# Mixer_coupler.net
KiCad netlist of a schematic drawn in Altium Designer
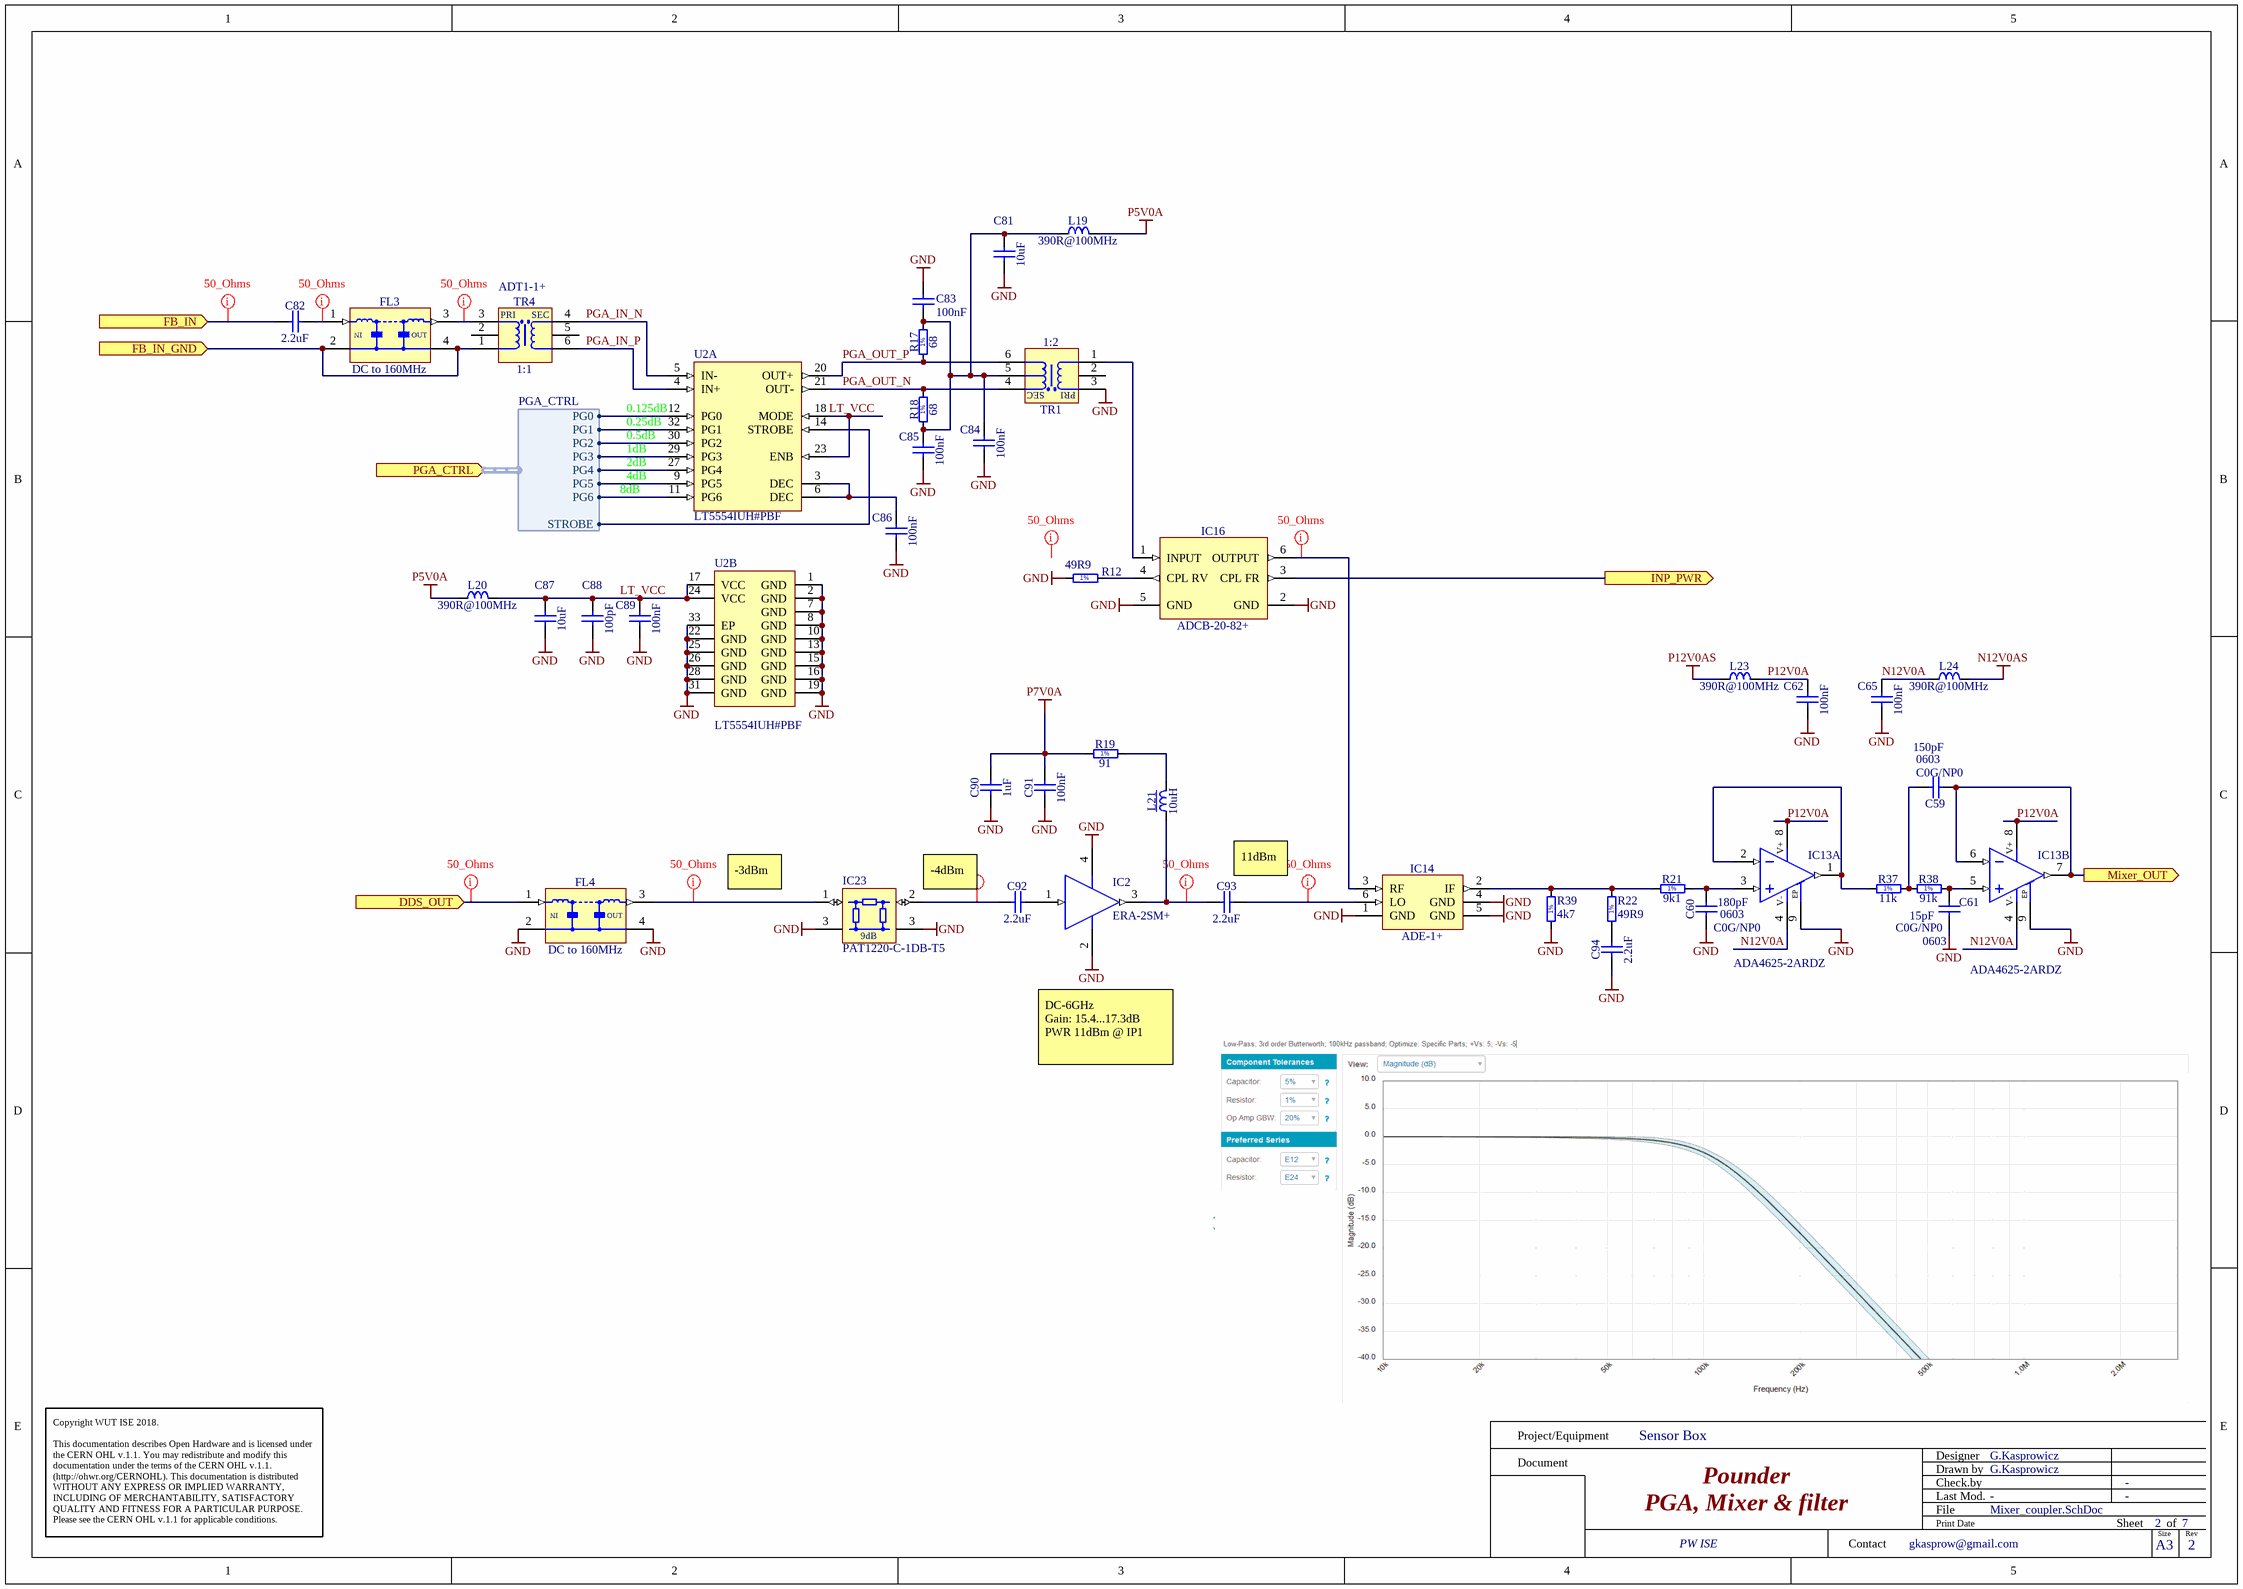
[diagram p0: Mixer_coupler.SchDoc]

(export (version "E")
  (design (tool "Eeschema 10.0.6"))
  (components
    (comp (ref "C59")
      (value "150pF")
      (footprint "CAPC1608X87N")
      (description "Non-polarised capacitor")
      (fields
        (field (name "PART NUMBER") "CC0603_150PF_50V_1%_NP0")
        (field (name "VOLTAGE") "50V")
        (field (name "TC") "C0G/NP0")
        (field (name "CASE") "0603")
        (field (name "AUTHOR") "CERN DEM MR")
      )
      (libsource (lib "Capacitors") (part "Capacitor - non polarized"))
    )
    (comp (ref "C60")
      (value "180pF")
      (footprint "CAPC1608X87N")
      (description "Non-polarised capacitor")
      (fields
        (field (name "PART NUMBER") "CC0603_180PF_50V_5%_NP0")
        (field (name "VOLTAGE") "50V")
        (field (name "TC") "C0G/NP0")
        (field (name "CASE") "0603")
        (field (name "AUTHOR") "CERN DEM JLC")
      )
      (libsource (lib "Capacitors") (part "Capacitor - non polarized"))
    )
    (comp (ref "C61")
      (value "15pF")
      (footprint "CAPC1608X87N")
      (description "Non-polarised capacitor")
      (fields
        (field (name "PART NUMBER") "CC0603_15PF_50V_5%_NP0")
        (field (name "VOLTAGE") "50V")
        (field (name "TC") "C0G/NP0")
        (field (name "CASE") "0603")
        (field (name "AUTHOR") "CERN DEM JLC")
      )
      (libsource (lib "Capacitors") (part "Capacitor - non polarized"))
    )
    (comp (ref "C62")
      (value "100nF")
      (footprint "CAPC1005X55N")
      (description "Non-polarised capacitor")
      (fields
        (field (name "PART NUMBER") "CC0402_100NF_16V_10%_X7R")
        (field (name "VOLTAGE") "16V")
        (field (name "AUTHOR") "CERN DEM JLC")
      )
      (libsource (lib "Capacitors") (part "Capacitor - non polarized"))
    )
    (comp (ref "C65")
      (value "100nF")
      (footprint "CAPC1005X55N")
      (description "Non-polarised capacitor")
      (fields
        (field (name "PART NUMBER") "CC0402_100NF_16V_10%_X7R")
        (field (name "VOLTAGE") "16V")
        (field (name "AUTHOR") "CERN DEM JLC")
      )
      (libsource (lib "Capacitors") (part "Capacitor - non polarized"))
    )
    (comp (ref "C81")
      (value "10uF")
      (footprint "CAPC1608X80N")
      (description "Non-polarised capacitor")
      (fields
        (field (name "PART NUMBER") "CC0603_10UF_16V_20%_X5R")
        (field (name "VOLTAGE") "16V")
        (field (name "AUTHOR") "CERN DEM MR")
      )
      (libsource (lib "Capacitors") (part "Capacitor - non polarized"))
    )
    (comp (ref "C82")
      (value "2.2uF")
      (footprint "CAPC1005X55N")
      (description "Non-polarised capacitor")
      (fields
        (field (name "PART NUMBER") "CC0402_2.2UF_6.3V_10%_X5R")
        (field (name "VOLTAGE") "6.3V")
        (field (name "AUTHOR") "CERN DEM JMW")
      )
      (libsource (lib "Capacitors") (part "Capacitor - non polarized"))
    )
    (comp (ref "C83")
      (value "100nF")
      (footprint "CAPC1005X55N")
      (description "Non-polarised capacitor")
      (fields
        (field (name "PART NUMBER") "CC0402_100NF_16V_10%_X7R")
        (field (name "VOLTAGE") "16V")
        (field (name "AUTHOR") "CERN DEM JLC")
      )
      (libsource (lib "Capacitors") (part "Capacitor - non polarized"))
    )
    (comp (ref "C84")
      (value "100nF")
      (footprint "CAPC1005X55N")
      (description "Non-polarised capacitor")
      (fields
        (field (name "PART NUMBER") "CC0402_100NF_16V_10%_X7R")
        (field (name "VOLTAGE") "16V")
        (field (name "AUTHOR") "CERN DEM JLC")
      )
      (libsource (lib "Capacitors") (part "Capacitor - non polarized"))
    )
    (comp (ref "C85")
      (value "100nF")
      (footprint "CAPC1005X55N")
      (description "Non-polarised capacitor")
      (fields
        (field (name "PART NUMBER") "CC0402_100NF_16V_10%_X7R")
        (field (name "VOLTAGE") "16V")
        (field (name "AUTHOR") "CERN DEM JLC")
      )
      (libsource (lib "Capacitors") (part "Capacitor - non polarized"))
    )
    (comp (ref "C86")
      (value "100nF")
      (footprint "CAPC1005X55N")
      (description "Non-polarised capacitor")
      (fields
        (field (name "PART NUMBER") "CC0402_100NF_16V_10%_X7R")
        (field (name "VOLTAGE") "16V")
        (field (name "AUTHOR") "CERN DEM JLC")
      )
      (libsource (lib "Capacitors") (part "Capacitor - non polarized"))
    )
    (comp (ref "C87")
      (value "10uF")
      (footprint "CAPC1608X80N")
      (description "Non-polarised capacitor")
      (fields
        (field (name "PART NUMBER") "CC0603_10UF_16V_20%_X5R")
        (field (name "VOLTAGE") "16V")
        (field (name "AUTHOR") "CERN DEM MR")
      )
      (libsource (lib "Capacitors") (part "Capacitor - non polarized"))
    )
    (comp (ref "C88")
      (value "100pF")
      (footprint "CAPC1005X55N")
      (description "Non-polarised capacitor")
      (fields
        (field (name "PART NUMBER") "CC0402_100PF_50V_5%_C0G")
        (field (name "VOLTAGE") "50V")
        (field (name "AUTHOR") "CERN DEM JLC")
      )
      (libsource (lib "Capacitors") (part "Capacitor - non polarized"))
    )
    (comp (ref "C89")
      (value "100nF")
      (footprint "CAPC1005X55N")
      (description "Non-polarised capacitor")
      (fields
        (field (name "PART NUMBER") "CC0402_100NF_16V_10%_X7R")
        (field (name "VOLTAGE") "16V")
        (field (name "AUTHOR") "CERN DEM JLC")
      )
      (libsource (lib "Capacitors") (part "Capacitor - non polarized"))
    )
    (comp (ref "C90")
      (value "1uF")
      (footprint "CAPC2012X140N")
      (description "Non-polarised capacitor")
      (fields
        (field (name "PART NUMBER") "CC0805_1UF_35V_20%_X7R")
        (field (name "VOLTAGE") "35V")
        (field (name "AUTHOR") "CERN DEM JLC")
      )
      (libsource (lib "Capacitors") (part "Capacitor - non polarized"))
    )
    (comp (ref "C91")
      (value "100nF")
      (footprint "CAPC1005X55N")
      (description "Non-polarised capacitor")
      (fields
        (field (name "PART NUMBER") "CC0402_100NF_16V_10%_X5R")
        (field (name "VOLTAGE") "16V")
        (field (name "AUTHOR") "CERN DEM JLC")
      )
      (libsource (lib "Capacitors") (part "Capacitor - non polarized"))
    )
    (comp (ref "C92")
      (value "2.2uF")
      (footprint "CAPC1005X55N")
      (description "Non-polarised capacitor")
      (fields
        (field (name "PART NUMBER") "CC0402_2.2UF_6.3V_10%_X5R")
        (field (name "VOLTAGE") "6.3V")
        (field (name "AUTHOR") "CERN DEM JMW")
      )
      (libsource (lib "Capacitors") (part "Capacitor - non polarized"))
    )
    (comp (ref "C93")
      (value "2.2uF")
      (footprint "CAPC1005X55N")
      (description "Non-polarised capacitor")
      (fields
        (field (name "PART NUMBER") "CC0402_2.2UF_6.3V_10%_X5R")
        (field (name "VOLTAGE") "6.3V")
        (field (name "AUTHOR") "CERN DEM JMW")
      )
      (libsource (lib "Capacitors") (part "Capacitor - non polarized"))
    )
    (comp (ref "C94")
      (value "2.2uF")
      (footprint "CAPC1005X55N")
      (description "Non-polarised capacitor")
      (fields
        (field (name "PART NUMBER") "CC0402_2.2UF_6.3V_10%_X5R")
        (field (name "VOLTAGE") "6.3V")
        (field (name "AUTHOR") "CERN DEM JMW")
      )
      (libsource (lib "Capacitors") (part "Capacitor - non polarized"))
    )
    (comp (ref "FL3")
      (value "DC to 160MHz")
      (footprint "FIL_MINI-CIRCUITS_FV1206")
      (description "50 Ohm DC to 320MHz Low Pass Filter")
      (fields
        (field (name "PART NUMBER") "FIL_MINI-CIRCUITS_LFCN-160")
        (field (name "MANUFACTURER") "MINI-CIRCUITS")
        (field (name "AUTHOR") "CERN DEM JLC")
      )
      (libsource (lib "LIBRARY_SCH") (part "FIL_MINI-CIRCUITS_LFCN-320"))
    )
    (comp (ref "FL4")
      (value "DC to 160MHz")
      (footprint "FIL_MINI-CIRCUITS_FV1206")
      (description "50 Ohm DC to 320MHz Low Pass Filter")
      (fields
        (field (name "PART NUMBER") "FIL_MINI-CIRCUITS_LFCN-160")
        (field (name "MANUFACTURER") "MINI-CIRCUITS")
        (field (name "AUTHOR") "CERN DEM JLC")
      )
      (libsource (lib "LIBRARY_SCH") (part "FIL_MINI-CIRCUITS_LFCN-320"))
    )
    (comp (ref "IC2")
      (value "ERA-2SM+")
      (footprint "MINI-CIRCUITS_WW107")
      (description "Monolithic Amplifier")
      (fields (field (name "MANUFACTURER") "MINI-CIRCUITS") (field (name "AUTHOR") "CERN DEM JLC"))
      (libsource (lib "ICs And Semiconductors") (part "Monolithic Amplifier Type 1"))
    )
    (comp (ref "IC13")
      (value "ADA4625-2ARDZ")
      (footprint "SOIC127P600X175-9N-S229")
      (description "Dual Operational Amplifier With Exposed Pad")
      (fields (field (name "MANUFACTURER") "ANALOG DEVICES") (field (name "AUTHOR") "CERN DEM MR"))
      (libsource (lib "ICs And Semiconductors") (part "Operational Amplifier x2 Type1 EP"))
    )
    (comp (ref "IC14")
      (value "ADE-1+")
      (footprint "MACOM_SM-87")
      (description "5 to 2500 MHz E-Series Surface Mount Mixer")
      (fields (field (name "MANUFACTURER") "MACOM") (field (name "AUTHOR") "CERN DEM JLC"))
      (libsource (lib "ICs And Semiconductors") (part "MAMX-007238-CM25MH"))
    )
    (comp (ref "IC16")
      (value "ADCB-20-82+")
      (footprint "MINI-CIRCUITS_CD637")
      (description "50Ω,   20dB Coupling,    1 to 800 MHz")
      (fields (field (name "MANUFACTURER") "MINI-CIRCUITS") (field (name "AUTHOR") "CERN DEM MR"))
      (libsource (lib "ICs And Semiconductors") (part "ADPQ-2-250"))
    )
    (comp (ref "IC23")
      (value "PAT1220-C-1DB-T5")
      (footprint "SUSUMU_PAT1220")
      (description "DC to 10GHz, 100mw, 50 Ohm, 9dB, Precision chip attenuator")
      (fields (field (name "MANUFACTURER") "SUSUMU") (field (name "AUTHOR") "GK"))
      (libsource (lib "LIBRARY_SCH") (part "RF_PAT1220-C-9DB-T5"))
    )
    (comp (ref "L19")
      (value "390R@100MHz")
      (footprint "INDC1608X95N")
      (description "Inductor")
      (fields
        (field (name "PART NUMBER") "IND0603_TDK_MPZ1608R391A")
        (field (name "POWER") "1.2A")
        (field (name "AUTHOR") "CERN DEM JLC")
      )
      (libsource (lib "Inductors & Transformers") (part "Inductor"))
    )
    (comp (ref "L20")
      (value "390R@100MHz")
      (footprint "INDC1608X95N")
      (description "Inductor")
      (fields
        (field (name "PART NUMBER") "IND0603_TDK_MPZ1608R391A")
        (field (name "POWER") "1.2A")
        (field (name "AUTHOR") "CERN DEM JLC")
      )
      (libsource (lib "Inductors & Transformers") (part "Inductor"))
    )
    (comp (ref "L21")
      (value "10uH")
      (footprint "IND_MURATA_LQH32C")
      (description "Inductor With Core")
      (fields
        (field (name "PART NUMBER") "IND_10UH_10%_MURATA_LQH32CN100K33L")
        (field (name "POWER") "450mA")
        (field (name "AUTHOR") "CERN DEM JLC")
      )
      (libsource (lib "Inductors & Transformers") (part "Inductor With Magnetic core"))
    )
    (comp (ref "L23")
      (value "390R@100MHz")
      (footprint "INDC1608X95N")
      (description "Inductor")
      (fields
        (field (name "PART NUMBER") "IND0603_TDK_MPZ1608R391A")
        (field (name "POWER") "1.2A")
        (field (name "AUTHOR") "CERN DEM JLC")
      )
      (libsource (lib "Inductors & Transformers") (part "Inductor"))
    )
    (comp (ref "L24")
      (value "390R@100MHz")
      (footprint "INDC1608X95N")
      (description "Inductor")
      (fields
        (field (name "PART NUMBER") "IND0603_TDK_MPZ1608R391A")
        (field (name "POWER") "1.2A")
        (field (name "AUTHOR") "CERN DEM JLC")
      )
      (libsource (lib "Inductors & Transformers") (part "Inductor"))
    )
    (comp (ref "R12")
      (value "49R9")
      (footprint "RESC1005X40N")
      (description "Resistor - 1%")
      (fields
        (field (name "PART NUMBER") "R0402_49R9_1%_0.0625W_100PPM")
        (field (name "POWER") "0.0625W")
        (field (name "AUTHOR") "CERN DEM JLC")
      )
      (libsource (lib "Resistors") (part "Resistor - 1%"))
    )
    (comp (ref "R17")
      (value "68")
      (footprint "RESC1608X55N")
      (description "Resistor - 1%")
      (fields
        (field (name "PART NUMBER") "R0603_68R_1%_0.1W_100PPM")
        (field (name "POWER") "0.1W")
        (field (name "AUTHOR") "CERN DEM JLC")
      )
      (libsource (lib "Resistors") (part "Resistor - 1%"))
    )
    (comp (ref "R18")
      (value "68")
      (footprint "RESC1608X55N")
      (description "Resistor - 1%")
      (fields
        (field (name "PART NUMBER") "R0603_68R_1%_0.1W_100PPM")
        (field (name "POWER") "0.1W")
        (field (name "AUTHOR") "CERN DEM JLC")
      )
      (libsource (lib "Resistors") (part "Resistor - 1%"))
    )
    (comp (ref "R19")
      (value "91")
      (footprint "RESC3216X65N")
      (description "Resistor - 1%")
      (fields
        (field (name "PART NUMBER") "R1206_91R_1%_0.25W_100PPM")
        (field (name "POWER") "0.25W")
        (field (name "AUTHOR") "CERN DEM JLC")
      )
      (libsource (lib "Resistors") (part "Resistor - 1%"))
    )
    (comp (ref "R21")
      (value "9k1")
      (footprint "RESC1005X40N")
      (description "Resistor - 1%")
      (fields
        (field (name "PART NUMBER") "R0402_9K1_1%_0.0625W_100PPM")
        (field (name "POWER") "0.0625W")
        (field (name "AUTHOR") "CERN DEM JLC")
      )
      (libsource (lib "Resistors") (part "Resistor - 1%"))
    )
    (comp (ref "R22")
      (value "49R9")
      (footprint "RESC1005X40N")
      (description "Resistor - 1%")
      (fields
        (field (name "PART NUMBER") "R0402_49R9_1%_0.0625W_100PPM")
        (field (name "POWER") "0.0625W")
        (field (name "AUTHOR") "CERN DEM JLC")
      )
      (libsource (lib "Resistors") (part "Resistor - 1%"))
    )
    (comp (ref "R37")
      (value "11k")
      (footprint "RESC1608X55N")
      (description "Resistor - 1%")
      (fields
        (field (name "PART NUMBER") "R0603_11K_1%_0.1W_100PPM")
        (field (name "POWER") "0.1W")
        (field (name "AUTHOR") "CERN DEM JLC")
      )
      (libsource (lib "Resistors") (part "Resistor - 1%"))
    )
    (comp (ref "R38")
      (value "91k")
      (footprint "RESC1608X55N")
      (description "Resistor - 1%")
      (fields
        (field (name "PART NUMBER") "R0603_91K_1%_0.1W_100PPM")
        (field (name "POWER") "0.1W")
        (field (name "AUTHOR") "CERN DEM JLC")
      )
      (libsource (lib "Resistors") (part "Resistor - 1%"))
    )
    (comp (ref "R39")
      (value "4k7")
      (footprint "RESC1005X40N")
      (description "Resistor - 1%")
      (fields
        (field (name "PART NUMBER") "R0402_4K7_1%_0.0625W_100PPM")
        (field (name "POWER") "0.0625W")
        (field (name "AUTHOR") "CERN DEM JLC")
      )
      (libsource (lib "Resistors") (part "Resistor - 1%"))
    )
    (comp (ref "TR1")
      (value "1:2")
      (footprint "XFMR_MINI-CIRCUITS_CD542")
      (description "50 Ohms 0.4 To 450MHz RF Transformer")
      (fields
        (field (name "PART NUMBER") "XFMR_MINI-CIRCUITS_ADT2-1T+")
        (field (name "MANUFACTURER") "MINI-CIRCUITS")
        (field (name "AUTHOR") "CERN DEM MR")
      )
      (libsource (lib "Inductors & Transformers") (part "XFMR_MINI-CIRCUITS_ADT2-1T-1P+"))
    )
    (comp (ref "TR4")
      (value "1:1")
      (footprint "XFMR_MINI-CIRCUITS_CD542")
      (description "50 Ohm 0.15 To 400MHz RF Transformers")
      (fields
        (field (name "PART NUMBER") "XFMR_MINI-CIRCUITS_ADT1-1+")
        (field (name "MANUFACTURER") "MINI-CIRCUITS")
        (field (name "MANUFACTURER PART NUMBER") "ADT1-1+")
        (field (name "AUTHOR") "CERN DEM JLC")
      )
      (libsource (lib "Inductors & Transformers") (part "XFMR_MINI-CIRCUITS_ADT1-1+"))
    )
    (comp (ref "U2")
      (value "LT5554IUH#PBF")
      (footprint "LT-UH-32_N")
      (fields
        (field (name "LINEAR TECHNOLOGY PART NUMBER") "LT5554")
        (field (name "MANUFACTURER") "Linear Technology")
      )
      (libsource (lib "Altium Content Vault") (part "LT-LT5554-UH-32"))
    )
  )
  (nets
    (net (code "2") (name "/DDS_OUT") (class "Default")
      (node (ref "FL4") (pin "1") (pinfunction "RFIN_1") (pintype "input"))
    )
    (net (code "3") (name "/FB_IN") (class "Default")
      (node (ref "C82") (pin "1") (pinfunction "1_1") (pintype "passive"))
    )
    (net (code "4") (name "/FB_IN_GND") (class "Default")
      (node (ref "FL3") (pin "2") (pinfunction "GND_2") (pintype "power_in"))
      (node (ref "FL3") (pin "4") (pinfunction "GND_4") (pintype "power_in"))
      (node (ref "TR4") (pin "1") (pinfunction "P_1") (pintype "passive"))
    )
    (net (code "5") (name "/INP_PWR") (class "Default")
      (node (ref "IC16") (pin "3") (pinfunction "CPL_FR_3") (pintype "output"))
    )
    (net (code "6") (name "/LT_VCC") (class "Default")
      (node (ref "C87") (pin "2") (pinfunction "2_2") (pintype "passive"))
      (node (ref "C88") (pin "2") (pinfunction "2_2") (pintype "passive"))
      (node (ref "C89") (pin "2") (pinfunction "2_2") (pintype "passive"))
      (node (ref "L20") (pin "2") (pinfunction "2_2") (pintype "passive"))
      (node (ref "U2") (pin "17") (pinfunction "VCC_17") (pintype "power_in"))
      (node (ref "U2") (pin "18") (pinfunction "MODE_18") (pintype "input"))
      (node (ref "U2") (pin "23") (pinfunction "ENB_23") (pintype "input"))
      (node (ref "U2") (pin "24") (pinfunction "VCC_24") (pintype "power_in"))
    )
    (net (code "7") (name "/Mixer_OUT") (class "Default")
      (node (ref "C59") (pin "1") (pinfunction "1_1") (pintype "passive"))
      (node (ref "IC13") (pin "6") (pinfunction "IN-_6") (pintype "input"))
      (node (ref "IC13") (pin "7") (pinfunction "OUT_7") (pintype "output"))
    )
    (net (code "8") (name "/N12V0A") (class "Default")
      (node (ref "C65") (pin "2") (pinfunction "2_2") (pintype "passive"))
      (node (ref "IC13") (pin "4") (pinfunction "V-_4") (pintype "power_in"))
      (node (ref "L24") (pin "1") (pinfunction "1_1") (pintype "passive"))
    )
    (net (code "9") (name "/P12V0A") (class "Default")
      (node (ref "C62") (pin "2") (pinfunction "2_2") (pintype "passive"))
      (node (ref "IC13") (pin "8") (pinfunction "V+_8") (pintype "power_in"))
      (node (ref "L23") (pin "2") (pinfunction "2_2") (pintype "passive"))
    )
    (net (code "10") (name "/PG0") (class "Default")
      (node (ref "U2") (pin "12") (pinfunction "PG0_12") (pintype "input"))
    )
    (net (code "11") (name "/PG1") (class "Default")
      (node (ref "U2") (pin "32") (pinfunction "PG1_32") (pintype "input"))
    )
    (net (code "12") (name "/PG2") (class "Default")
      (node (ref "U2") (pin "30") (pinfunction "PG2_30") (pintype "input"))
    )
    (net (code "13") (name "/PG3") (class "Default")
      (node (ref "U2") (pin "29") (pinfunction "PG3_29") (pintype "input"))
    )
    (net (code "14") (name "/PG4") (class "Default")
      (node (ref "U2") (pin "27") (pinfunction "PG4_27") (pintype "input"))
    )
    (net (code "15") (name "/PG5") (class "Default")
      (node (ref "U2") (pin "9") (pinfunction "PG5_9") (pintype "input"))
    )
    (net (code "16") (name "/PG6") (class "Default")
      (node (ref "U2") (pin "11") (pinfunction "PG6_11") (pintype "input"))
    )
    (net (code "17") (name "/PGA_IN_N") (class "Default")
      (node (ref "TR4") (pin "4") (pinfunction "SDOT_4") (pintype "passive"))
      (node (ref "U2") (pin "5") (pinfunction "IN-_5") (pintype "input"))
    )
    (net (code "18") (name "/PGA_IN_P") (class "Default")
      (node (ref "TR4") (pin "6") (pinfunction "S_6") (pintype "passive"))
      (node (ref "U2") (pin "4") (pinfunction "IN+_4") (pintype "input"))
    )
    (net (code "19") (name "/PGA_OUT_N") (class "Default")
      (node (ref "R18") (pin "2") (pinfunction "2_2") (pintype "passive"))
      (node (ref "TR1") (pin "4") (pinfunction "S_4") (pintype "passive"))
      (node (ref "U2") (pin "21") (pinfunction "OUT-_21") (pintype "output"))
    )
    (net (code "20") (name "/PGA_OUT_P") (class "Default")
      (node (ref "R17") (pin "1") (pinfunction "1_1") (pintype "passive"))
      (node (ref "TR1") (pin "6") (pinfunction "SDOT_6") (pintype "passive"))
      (node (ref "U2") (pin "20") (pinfunction "OUT+_20") (pintype "output"))
    )
    (net (code "21") (name "/STROBE") (class "Default")
      (node (ref "U2") (pin "14") (pinfunction "STROBE_14") (pintype "input"))
    )
    (net (code "23") (name "GND") (class "Default")
      (node (ref "C60") (pin "1") (pinfunction "1_1") (pintype "passive"))
      (node (ref "C61") (pin "1") (pinfunction "1_1") (pintype "passive"))
      (node (ref "C62") (pin "1") (pinfunction "1_1") (pintype "passive"))
      (node (ref "C65") (pin "1") (pinfunction "1_1") (pintype "passive"))
      (node (ref "C81") (pin "1") (pinfunction "1_1") (pintype "passive"))
      (node (ref "C83") (pin "1") (pinfunction "1_1") (pintype "passive"))
      (node (ref "C84") (pin "1") (pinfunction "1_1") (pintype "passive"))
      (node (ref "C85") (pin "1") (pinfunction "1_1") (pintype "passive"))
      (node (ref "C86") (pin "1") (pinfunction "1_1") (pintype "passive"))
      (node (ref "C87") (pin "1") (pinfunction "1_1") (pintype "passive"))
      (node (ref "C88") (pin "1") (pinfunction "1_1") (pintype "passive"))
      (node (ref "C89") (pin "1") (pinfunction "1_1") (pintype "passive"))
      (node (ref "C90") (pin "1") (pinfunction "1_1") (pintype "passive"))
      (node (ref "C91") (pin "1") (pinfunction "1_1") (pintype "passive"))
      (node (ref "C94") (pin "1") (pinfunction "1_1") (pintype "passive"))
      (node (ref "FL4") (pin "2") (pinfunction "GND_2") (pintype "power_in"))
      (node (ref "FL4") (pin "4") (pinfunction "GND_4") (pintype "power_in"))
      (node (ref "IC13") (pin "9") (pinfunction "Exposed_Pad_9") (pintype "power_in"))
      (node (ref "IC14") (pin "1") (pinfunction "GND_1") (pintype "power_in"))
      (node (ref "IC14") (pin "4") (pinfunction "GND_4") (pintype "power_in"))
      (node (ref "IC14") (pin "5") (pinfunction "GND_5") (pintype "power_in"))
      (node (ref "IC16") (pin "2") (pinfunction "GND_2") (pintype "power_in"))
      (node (ref "IC16") (pin "5") (pinfunction "GND_5") (pintype "power_in"))
      (node (ref "IC2") (pin "2") (pinfunction "GND_2") (pintype "power_in"))
      (node (ref "IC2") (pin "4") (pinfunction "GND_4") (pintype "power_in"))
      (node (ref "IC23") (pin "3") (pinfunction "GND_3") (pintype "passive"))
      (node (ref "R12") (pin "1") (pinfunction "1_1") (pintype "passive"))
      (node (ref "R39") (pin "1") (pinfunction "1_1") (pintype "passive"))
      (node (ref "TR1") (pin "3") (pinfunction "PDOT_3") (pintype "passive"))
      (node (ref "U2") (pin "1") (pinfunction "GND_1") (pintype "power_in"))
      (node (ref "U2") (pin "10") (pinfunction "GND_10") (pintype "power_in"))
      (node (ref "U2") (pin "13") (pinfunction "GND_13") (pintype "power_in"))
      (node (ref "U2") (pin "15") (pinfunction "GND_15") (pintype "power_in"))
      (node (ref "U2") (pin "16") (pinfunction "GND_16") (pintype "power_in"))
      (node (ref "U2") (pin "19") (pinfunction "GND_19") (pintype "power_in"))
      (node (ref "U2") (pin "2") (pinfunction "GND_2") (pintype "power_in"))
      (node (ref "U2") (pin "22") (pinfunction "GND_22") (pintype "power_in"))
      (node (ref "U2") (pin "25") (pinfunction "GND_25") (pintype "power_in"))
      (node (ref "U2") (pin "26") (pinfunction "GND_26") (pintype "power_in"))
      (node (ref "U2") (pin "28") (pinfunction "GND_28") (pintype "power_in"))
      (node (ref "U2") (pin "31") (pinfunction "GND_31") (pintype "power_in"))
      (node (ref "U2") (pin "33") (pinfunction "EP_33") (pintype "power_in"))
      (node (ref "U2") (pin "7") (pinfunction "GND_7") (pintype "power_in"))
      (node (ref "U2") (pin "8") (pinfunction "GND_8") (pintype "power_in"))
    )
    (net (code "24") (name "N12V0AS") (class "Default")
      (node (ref "L24") (pin "2") (pinfunction "2_2") (pintype "passive"))
    )
    (net (code "25") (name "Net-(C59-Pad2)") (class "Default")
      (node (ref "C59") (pin "2") (pinfunction "2_2") (pintype "passive"))
      (node (ref "R37") (pin "2") (pinfunction "2_2") (pintype "passive"))
      (node (ref "R38") (pin "1") (pinfunction "1_1") (pintype "passive"))
    )
    (net (code "26") (name "Net-(C86-Pad2)") (class "Default")
      (node (ref "C86") (pin "2") (pinfunction "2_2") (pintype "passive"))
      (node (ref "U2") (pin "3") (pinfunction "DEC_3") (pintype "passive"))
      (node (ref "U2") (pin "6") (pinfunction "DEC_6") (pintype "passive"))
    )
    (net (code "27") (name "Net-(C94-Pad2)") (class "Default")
      (node (ref "C94") (pin "2") (pinfunction "2_2") (pintype "passive"))
      (node (ref "R22") (pin "1") (pinfunction "1_1") (pintype "passive"))
    )
    (net (code "28") (name "Net-(FL3-RFIN)") (class "Default")
      (node (ref "C82") (pin "2") (pinfunction "2_2") (pintype "passive"))
      (node (ref "FL3") (pin "1") (pinfunction "RFIN_1") (pintype "input"))
    )
    (net (code "29") (name "Net-(FL3-RFOUT)") (class "Default")
      (node (ref "FL3") (pin "3") (pinfunction "RFOUT_3") (pintype "output"))
      (node (ref "TR4") (pin "3") (pinfunction "PDOT_3") (pintype "passive"))
    )
    (net (code "30") (name "Net-(FL4-RFOUT)") (class "Default")
      (node (ref "FL4") (pin "3") (pinfunction "RFOUT_3") (pintype "output"))
      (node (ref "IC23") (pin "1") (pinfunction "IN_1") (pintype "bidirectional"))
    )
    (net (code "31") (name "Net-(IC2-RF_IN)") (class "Default")
      (node (ref "C92") (pin "2") (pinfunction "2_2") (pintype "passive"))
      (node (ref "IC2") (pin "1") (pinfunction "RF_IN_1") (pintype "input"))
    )
    (net (code "32") (name "Net-(IC2-RF_OUT)") (class "Default")
      (node (ref "C93") (pin "1") (pinfunction "1_1") (pintype "passive"))
      (node (ref "IC2") (pin "3") (pinfunction "RF_OUT_3") (pintype "output"))
      (node (ref "L21") (pin "1") (pinfunction "1_1") (pintype "passive"))
    )
    (net (code "33") (name "Net-(IC13A-IN+)") (class "Default")
      (node (ref "C60") (pin "2") (pinfunction "2_2") (pintype "passive"))
      (node (ref "IC13") (pin "3") (pinfunction "IN+_3") (pintype "input"))
      (node (ref "R21") (pin "2") (pinfunction "2_2") (pintype "passive"))
    )
    (net (code "34") (name "Net-(IC13A-IN-)") (class "Default")
      (node (ref "IC13") (pin "1") (pinfunction "OUT_1") (pintype "output"))
      (node (ref "IC13") (pin "2") (pinfunction "IN-_2") (pintype "input"))
      (node (ref "R37") (pin "1") (pinfunction "1_1") (pintype "passive"))
    )
    (net (code "35") (name "Net-(IC13B-IN+)") (class "Default")
      (node (ref "C61") (pin "2") (pinfunction "2_2") (pintype "passive"))
      (node (ref "IC13") (pin "5") (pinfunction "IN+_5") (pintype "input"))
      (node (ref "R38") (pin "2") (pinfunction "2_2") (pintype "passive"))
    )
    (net (code "36") (name "Net-(IC14-IF)") (class "Default")
      (node (ref "IC14") (pin "2") (pinfunction "IF_2") (pintype "output"))
      (node (ref "R21") (pin "1") (pinfunction "1_1") (pintype "passive"))
      (node (ref "R22") (pin "2") (pinfunction "2_2") (pintype "passive"))
      (node (ref "R39") (pin "2") (pinfunction "2_2") (pintype "passive"))
    )
    (net (code "37") (name "Net-(IC14-LO)") (class "Default")
      (node (ref "C93") (pin "2") (pinfunction "2_2") (pintype "passive"))
      (node (ref "IC14") (pin "6") (pinfunction "LO_6") (pintype "input"))
    )
    (net (code "38") (name "Net-(IC14-RF)") (class "Default")
      (node (ref "IC14") (pin "3") (pinfunction "RF_3") (pintype "input"))
      (node (ref "IC16") (pin "6") (pinfunction "OUTPUT_6") (pintype "output"))
    )
    (net (code "39") (name "Net-(IC16-CPL_RV)") (class "Default")
      (node (ref "IC16") (pin "4") (pinfunction "CPL_RV_4") (pintype "output"))
      (node (ref "R12") (pin "2") (pinfunction "2_2") (pintype "passive"))
    )
    (net (code "40") (name "Net-(IC16-INPUT)") (class "Default")
      (node (ref "IC16") (pin "1") (pinfunction "INPUT_1") (pintype "input"))
      (node (ref "TR1") (pin "1") (pinfunction "P_1") (pintype "passive"))
    )
    (net (code "41") (name "Net-(IC23-OUT)") (class "Default")
      (node (ref "C92") (pin "1") (pinfunction "1_1") (pintype "passive"))
      (node (ref "IC23") (pin "2") (pinfunction "OUT_2") (pintype "bidirectional"))
    )
    (net (code "42") (name "Net-(L21-Pad2)") (class "Default")
      (node (ref "L21") (pin "2") (pinfunction "2_2") (pintype "passive"))
      (node (ref "R19") (pin "2") (pinfunction "2_2") (pintype "passive"))
    )
    (net (code "43") (name "Net-(TR1-SCT)") (class "Default")
      (node (ref "C81") (pin "2") (pinfunction "2_2") (pintype "passive"))
      (node (ref "C83") (pin "2") (pinfunction "2_2") (pintype "passive"))
      (node (ref "C84") (pin "2") (pinfunction "2_2") (pintype "passive"))
      (node (ref "C85") (pin "2") (pinfunction "2_2") (pintype "passive"))
      (node (ref "L19") (pin "1") (pinfunction "1_1") (pintype "passive"))
      (node (ref "R17") (pin "2") (pinfunction "2_2") (pintype "passive"))
      (node (ref "R18") (pin "1") (pinfunction "1_1") (pintype "passive"))
      (node (ref "TR1") (pin "5") (pinfunction "SCT_5") (pintype "passive"))
    )
    (net (code "44") (name "P5V0A") (class "Default")
      (node (ref "L19") (pin "2") (pinfunction "2_2") (pintype "passive"))
      (node (ref "L20") (pin "1") (pinfunction "1_1") (pintype "passive"))
    )
    (net (code "45") (name "P7V0A") (class "Default")
      (node (ref "C90") (pin "2") (pinfunction "2_2") (pintype "passive"))
      (node (ref "C91") (pin "2") (pinfunction "2_2") (pintype "passive"))
      (node (ref "R19") (pin "1") (pinfunction "1_1") (pintype "passive"))
    )
    (net (code "46") (name "P12V0AS") (class "Default")
      (node (ref "L23") (pin "1") (pinfunction "1_1") (pintype "passive"))
    )
    (net (code "47") (name "unconnected-(TR1-NC-Pad2)") (class "Default")
      (node (ref "TR1") (pin "2") (pinfunction "NC_2") (pintype "passive"))
    )
    (net (code "48") (name "unconnected-(TR4-NC-Pad2)") (class "Default")
      (node (ref "TR4") (pin "2") (pinfunction "NC_2") (pintype "passive"))
    )
    (net (code "49") (name "unconnected-(TR4-NC-Pad5)") (class "Default")
      (node (ref "TR4") (pin "5") (pinfunction "NC_5") (pintype "passive"))
    )
  )
)
